# Sheet2.net
KiCad netlist of a schematic drawn in Altium Designer
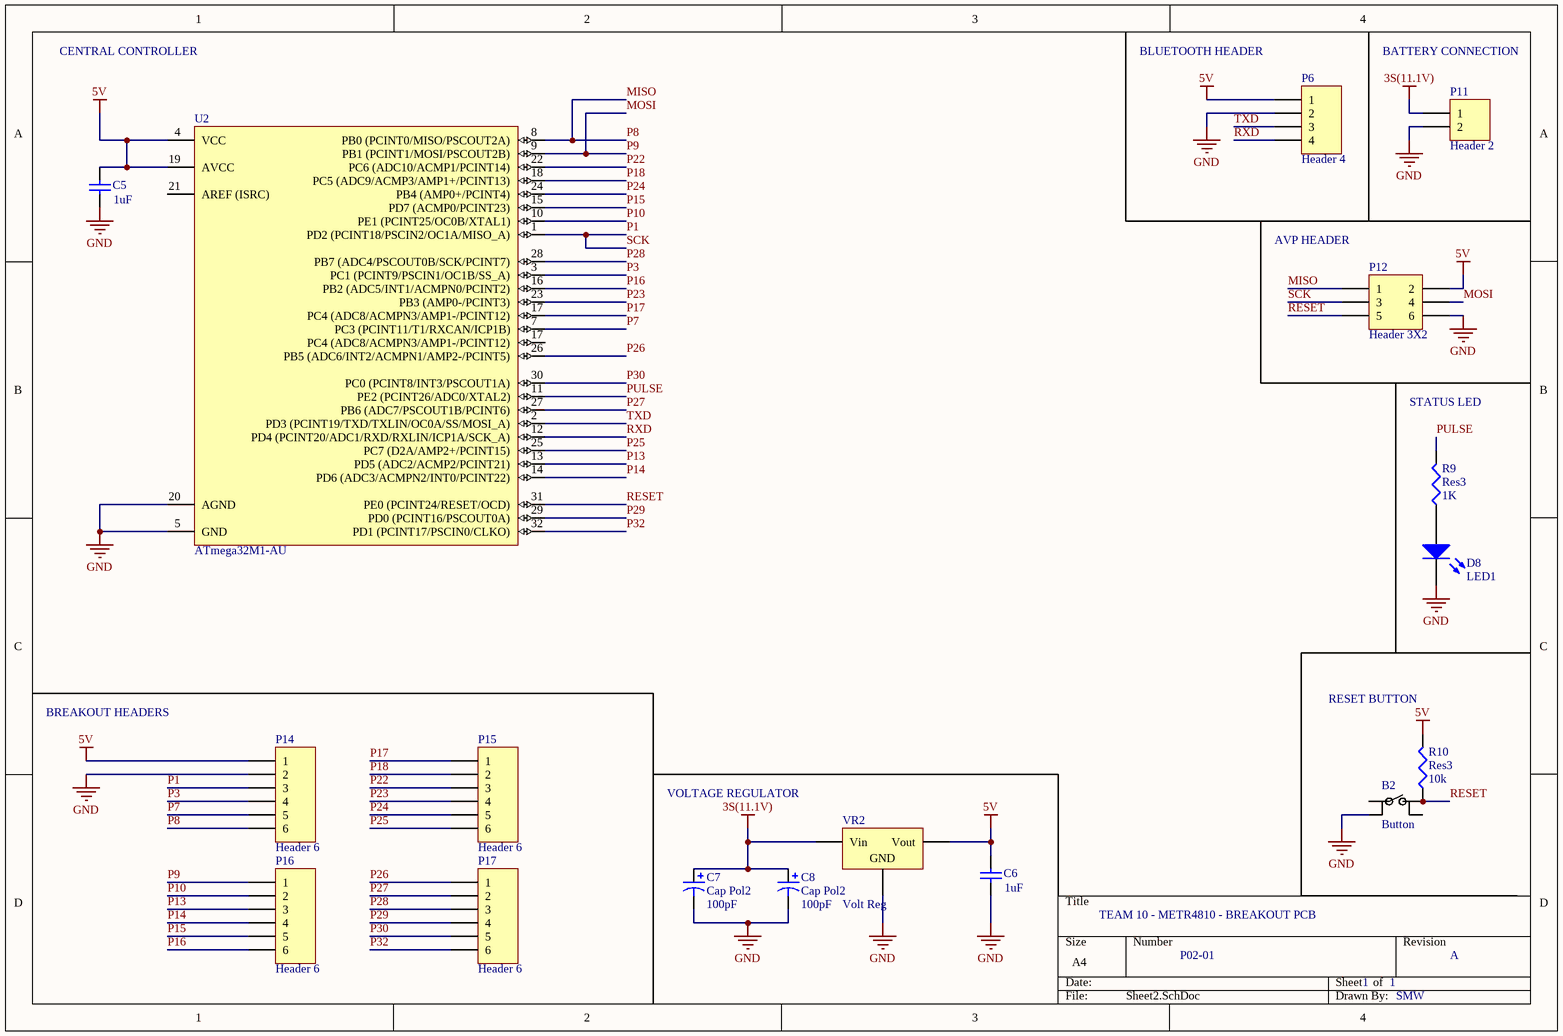
[diagram p0: Sheet2.SchDoc]

(export (version "E")
  (design (tool "Eeschema 10.0.6"))
  (components
    (comp (ref "B2")
      (value "Button")
      (footprint "SMT Tactile Button")
      (libsource (lib "WillsSchematicLibrary") (part "Switch"))
    )
    (comp (ref "C5")
      (value "1uF")
      (footprint "1608[0603]")
      (description "Capacitor")
      (fields (field (name "Comment") "Cap") (field (name "PUBLISHER") "Altium Limited"))
      (libsource (lib "Miscellaneous Devices") (part "Cap"))
    )
    (comp (ref "C6")
      (value "1uF")
      (footprint "1608[0603]")
      (description "Capacitor")
      (fields (field (name "Comment") "Cap") (field (name "PUBLISHER") "Altium Limited"))
      (libsource (lib "Miscellaneous Devices") (part "Cap"))
    )
    (comp (ref "C7")
      (value "Cap Pol2")
      (footprint "CAPAE9983X105M")
      (description "Polarized Capacitor (Axial)")
      (fields (field (name "ALTIUM_VALUE") "100pF") (field (name "PUBLISHER") "Altium Limited"))
      (libsource (lib "Miscellaneous Devices") (part "Cap Pol2"))
    )
    (comp (ref "C8")
      (value "Cap Pol2")
      (footprint "CAPAE9983X105M")
      (description "Polarized Capacitor (Axial)")
      (fields (field (name "ALTIUM_VALUE") "100pF") (field (name "PUBLISHER") "Altium Limited"))
      (libsource (lib "Miscellaneous Devices") (part "Cap Pol2"))
    )
    (comp (ref "D8")
      (value "LED1")
      (footprint "L0603")
      (description "Typical RED GaAs LED")
      (fields (field (name "PUBLISHER") "Altium Limited"))
      (libsource (lib "Miscellaneous Devices") (part "LED1"))
    )
    (comp (ref "P6")
      (value "Header 4")
      (footprint "HDR1X4")
      (description "Header, 4-Pin")
      (fields (field (name "PUBLISHER") "Altium Limited"))
      (libsource (lib "Miscellaneous Connectors") (part "Header 4"))
    )
    (comp (ref "P11")
      (value "Header 2")
      (footprint "HDR1X2")
      (description "Header, 2-Pin")
      (fields (field (name "PUBLISHER") "Altium Limited"))
      (libsource (lib "Miscellaneous Connectors") (part "Header 2"))
    )
    (comp (ref "P12")
      (value "Header 3X2")
      (footprint "HDR2X3")
      (description "Header, 3-Pin, Dual row")
      (fields (field (name "PUBLISHER") "Altium Limited"))
      (libsource (lib "Miscellaneous Connectors") (part "Header 3X2"))
    )
    (comp (ref "P14")
      (value "Header 6")
      (footprint "HDR1X6")
      (description "Header, 6-Pin")
      (fields (field (name "PUBLISHER") "Altium Limited"))
      (libsource (lib "Miscellaneous Connectors") (part "Header 6"))
    )
    (comp (ref "P15")
      (value "Header 6")
      (footprint "HDR1X6")
      (description "Header, 6-Pin")
      (fields (field (name "PUBLISHER") "Altium Limited"))
      (libsource (lib "Miscellaneous Connectors") (part "Header 6"))
    )
    (comp (ref "P16")
      (value "Header 6")
      (footprint "HDR1X6")
      (description "Header, 6-Pin")
      (fields (field (name "PUBLISHER") "Altium Limited"))
      (libsource (lib "Miscellaneous Connectors") (part "Header 6"))
    )
    (comp (ref "P17")
      (value "Header 6")
      (footprint "HDR1X6")
      (description "Header, 6-Pin")
      (fields (field (name "PUBLISHER") "Altium Limited"))
      (libsource (lib "Miscellaneous Connectors") (part "Header 6"))
    )
    (comp (ref "R9")
      (value "Res3")
      (footprint "J1-0603")
      (description "Resistor")
      (fields (field (name "ALTIUM_VALUE") "1K") (field (name "PUBLISHER") "Altium Limited"))
      (libsource (lib "Miscellaneous Devices") (part "Res3"))
    )
    (comp (ref "R10")
      (value "Res3")
      (footprint "J1-0603")
      (description "Resistor")
      (fields (field (name "ALTIUM_VALUE") "10k") (field (name "PUBLISHER") "Altium Limited"))
      (libsource (lib "Miscellaneous Devices") (part "Res3"))
    )
    (comp (ref "U2")
      (value "ATmega32M1-AU")
      (footprint "32A_L")
      (libsource (lib "Atmel Microcontroller AVR Automotive") (part "ATmega32M1-AU"))
    )
    (comp (ref "VR2")
      (value "Volt Reg")
      (footprint "D2PAK_N")
      (description "Voltage Regulator")
      (fields (field (name "PUBLISHER") "Altium Limited"))
      (libsource (lib "Miscellaneous Devices") (part "Volt Reg"))
    )
  )
  (nets
    (net (code "1") (name "/MISO") (class "Default")
      (node (ref "P12") (pin "1") (pinfunction "1_1") (pintype "passive"))
      (node (ref "P14") (pin "6") (pinfunction "6_6") (pintype "passive"))
      (node (ref "U2") (pin "8") (pinfunction "PB0_(PCINT0/MISO/PSCOUT2A)_8") (pintype "bidirectional"))
    )
    (net (code "2") (name "/MOSI") (class "Default")
      (node (ref "P12") (pin "4") (pinfunction "4_4") (pintype "passive"))
      (node (ref "P16") (pin "1") (pinfunction "1_1") (pintype "passive"))
      (node (ref "U2") (pin "9") (pinfunction "PB1_(PCINT1/MOSI/PSCOUT2B)_9") (pintype "bidirectional"))
    )
    (net (code "3") (name "/P1") (class "Default")
      (node (ref "P12") (pin "3") (pinfunction "3_3") (pintype "passive"))
      (node (ref "P14") (pin "3") (pinfunction "3_3") (pintype "passive"))
      (node (ref "U2") (pin "1") (pinfunction "PD2_(PCINT18/PSCIN2/OC1A/MISO_A)_1") (pintype "bidirectional"))
    )
    (net (code "4") (name "/P3") (class "Default")
      (node (ref "P14") (pin "4") (pinfunction "4_4") (pintype "passive"))
      (node (ref "U2") (pin "3") (pinfunction "PC1_(PCINT9/PSCIN1/OC1B/SS_A)_3") (pintype "bidirectional"))
    )
    (net (code "5") (name "/P7") (class "Default")
      (node (ref "P14") (pin "5") (pinfunction "5_5") (pintype "passive"))
      (node (ref "U2") (pin "7") (pinfunction "PC3_(PCINT11/T1/RXCAN/ICP1B)_7") (pintype "bidirectional"))
    )
    (net (code "6") (name "/P10") (class "Default")
      (node (ref "P16") (pin "2") (pinfunction "2_2") (pintype "passive"))
      (node (ref "U2") (pin "10") (pinfunction "PE1_(PCINT25/OC0B/XTAL1)_10") (pintype "bidirectional"))
    )
    (net (code "7") (name "/P13") (class "Default")
      (node (ref "P16") (pin "3") (pinfunction "3_3") (pintype "passive"))
      (node (ref "U2") (pin "13") (pinfunction "PD5_(ADC2/ACMP2/PCINT21)_13") (pintype "bidirectional"))
    )
    (net (code "8") (name "/P14") (class "Default")
      (node (ref "P16") (pin "4") (pinfunction "4_4") (pintype "passive"))
      (node (ref "U2") (pin "14") (pinfunction "PD6_(ADC3/ACMPN2/INT0/PCINT22)_14") (pintype "bidirectional"))
    )
    (net (code "9") (name "/P15") (class "Default")
      (node (ref "P16") (pin "5") (pinfunction "5_5") (pintype "passive"))
      (node (ref "U2") (pin "15") (pinfunction "PD7_(ACMP0/PCINT23)_15") (pintype "bidirectional"))
    )
    (net (code "10") (name "/P16") (class "Default")
      (node (ref "P16") (pin "6") (pinfunction "6_6") (pintype "passive"))
      (node (ref "U2") (pin "16") (pinfunction "PB2_(ADC5/INT1/ACMPN0/PCINT2)_16") (pintype "bidirectional"))
    )
    (net (code "11") (name "/P17") (class "Default")
      (node (ref "P15") (pin "1") (pinfunction "1_1") (pintype "passive"))
      (node (ref "U2") (pin "17") (pinfunction "PC4_(ADC8/ACMPN3/AMP1-/PCINT12)_17") (pintype "bidirectional"))
    )
    (net (code "12") (name "/P18") (class "Default")
      (node (ref "P15") (pin "2") (pinfunction "2_2") (pintype "passive"))
      (node (ref "U2") (pin "18") (pinfunction "PC5_(ADC9/ACMP3/AMP1+/PCINT13)_18") (pintype "bidirectional"))
    )
    (net (code "13") (name "/P22") (class "Default")
      (node (ref "P15") (pin "3") (pinfunction "3_3") (pintype "passive"))
      (node (ref "U2") (pin "22") (pinfunction "PC6_(ADC10/ACMP1/PCINT14)_22") (pintype "bidirectional"))
    )
    (net (code "14") (name "/P23") (class "Default")
      (node (ref "P15") (pin "4") (pinfunction "4_4") (pintype "passive"))
      (node (ref "U2") (pin "23") (pinfunction "PB3_(AMP0-/PCINT3)_23") (pintype "bidirectional"))
    )
    (net (code "15") (name "/P24") (class "Default")
      (node (ref "P15") (pin "5") (pinfunction "5_5") (pintype "passive"))
      (node (ref "U2") (pin "24") (pinfunction "PB4_(AMP0+/PCINT4)_24") (pintype "bidirectional"))
    )
    (net (code "16") (name "/P25") (class "Default")
      (node (ref "P15") (pin "6") (pinfunction "6_6") (pintype "passive"))
      (node (ref "U2") (pin "25") (pinfunction "PC7_(D2A/AMP2+/PCINT15)_25") (pintype "bidirectional"))
    )
    (net (code "17") (name "/P26") (class "Default")
      (node (ref "P17") (pin "1") (pinfunction "1_1") (pintype "passive"))
      (node (ref "U2") (pin "26") (pinfunction "PB5_(ADC6/INT2/ACMPN1/AMP2-/PCINT5)_26") (pintype "bidirectional"))
    )
    (net (code "18") (name "/P27") (class "Default")
      (node (ref "P17") (pin "2") (pinfunction "2_2") (pintype "passive"))
      (node (ref "U2") (pin "27") (pinfunction "PB6_(ADC7/PSCOUT1B/PCINT6)_27") (pintype "bidirectional"))
    )
    (net (code "19") (name "/P28") (class "Default")
      (node (ref "P17") (pin "3") (pinfunction "3_3") (pintype "passive"))
      (node (ref "U2") (pin "28") (pinfunction "PB7_(ADC4/PSCOUT0B/SCK/PCINT7)_28") (pintype "bidirectional"))
    )
    (net (code "20") (name "/P29") (class "Default")
      (node (ref "P17") (pin "4") (pinfunction "4_4") (pintype "passive"))
      (node (ref "U2") (pin "29") (pinfunction "PD0_(PCINT16/PSCOUT0A)_29") (pintype "bidirectional"))
    )
    (net (code "21") (name "/P30") (class "Default")
      (node (ref "P17") (pin "5") (pinfunction "5_5") (pintype "passive"))
      (node (ref "U2") (pin "30") (pinfunction "PC0_(PCINT8/INT3/PSCOUT1A)_30") (pintype "bidirectional"))
    )
    (net (code "22") (name "/P32") (class "Default")
      (node (ref "P17") (pin "6") (pinfunction "6_6") (pintype "passive"))
      (node (ref "U2") (pin "32") (pinfunction "PD1_(PCINT17/PSCIN0/CLKO)_32") (pintype "bidirectional"))
    )
    (net (code "23") (name "/PULSE") (class "Default")
      (node (ref "R9") (pin "2") (pinfunction "2_2") (pintype "passive"))
      (node (ref "U2") (pin "11") (pinfunction "PE2_(PCINT26/ADC0/XTAL2)_11") (pintype "bidirectional"))
    )
    (net (code "24") (name "/RESET") (class "Default")
      (node (ref "B2") (pin "4") (pinfunction "4_4") (pintype "passive"))
      (node (ref "P12") (pin "5") (pinfunction "5_5") (pintype "passive"))
      (node (ref "R10") (pin "1") (pinfunction "1_1") (pintype "passive"))
      (node (ref "U2") (pin "31") (pinfunction "PE0_(PCINT24/RESET/OCD)_31") (pintype "bidirectional"))
    )
    (net (code "25") (name "/RXD") (class "Default")
      (node (ref "P6") (pin "4") (pinfunction "4_4") (pintype "passive"))
      (node (ref "U2") (pin "12") (pinfunction "PD4_(PCINT20/ADC1/RXD/RXLIN/ICP1A/SCK_A)_12") (pintype "bidirectional"))
    )
    (net (code "26") (name "/TXD") (class "Default")
      (node (ref "P6") (pin "3") (pinfunction "3_3") (pintype "passive"))
      (node (ref "U2") (pin "2") (pinfunction "PD3_(PCINT19/TXD/TXLIN/OC0A/SS/MOSI_A)_2") (pintype "bidirectional"))
    )
    (net (code "27") (name "3S(11.1V)") (class "Default")
      (node (ref "C7") (pin "1") (pinfunction "1_1") (pintype "passive"))
      (node (ref "C8") (pin "1") (pinfunction "1_1") (pintype "passive"))
      (node (ref "P11") (pin "1") (pinfunction "1_1") (pintype "passive"))
      (node (ref "VR2") (pin "1") (pinfunction "Vin_1") (pintype "passive"))
    )
    (net (code "28") (name "5V") (class "Default")
      (node (ref "C5") (pin "2") (pinfunction "2_2") (pintype "passive"))
      (node (ref "C6") (pin "2") (pinfunction "2_2") (pintype "passive"))
      (node (ref "P12") (pin "2") (pinfunction "2_2") (pintype "passive"))
      (node (ref "P14") (pin "1") (pinfunction "1_1") (pintype "passive"))
      (node (ref "P6") (pin "1") (pinfunction "1_1") (pintype "passive"))
      (node (ref "R10") (pin "2") (pinfunction "2_2") (pintype "passive"))
      (node (ref "U2") (pin "19") (pinfunction "AVCC_19") (pintype "power_in"))
      (node (ref "U2") (pin "4") (pinfunction "VCC_4") (pintype "power_in"))
      (node (ref "VR2") (pin "3") (pinfunction "Vout_3") (pintype "passive"))
    )
    (net (code "29") (name "GND") (class "Default")
      (node (ref "B2") (pin "2") (pinfunction "2_2") (pintype "passive"))
      (node (ref "C5") (pin "1") (pinfunction "1_1") (pintype "passive"))
      (node (ref "C6") (pin "1") (pinfunction "1_1") (pintype "passive"))
      (node (ref "C7") (pin "2") (pinfunction "2_2") (pintype "passive"))
      (node (ref "C8") (pin "2") (pinfunction "2_2") (pintype "passive"))
      (node (ref "D8") (pin "2") (pinfunction "K_2") (pintype "passive"))
      (node (ref "P11") (pin "2") (pinfunction "2_2") (pintype "passive"))
      (node (ref "P12") (pin "6") (pinfunction "6_6") (pintype "passive"))
      (node (ref "P14") (pin "2") (pinfunction "2_2") (pintype "passive"))
      (node (ref "P6") (pin "2") (pinfunction "2_2") (pintype "passive"))
      (node (ref "U2") (pin "20") (pinfunction "AGND_20") (pintype "power_in"))
      (node (ref "U2") (pin "5") (pinfunction "GND_5") (pintype "power_in"))
      (node (ref "VR2") (pin "2") (pinfunction "GND_2") (pintype "passive"))
    )
    (net (code "30") (name "Net-(D8-A)") (class "Default")
      (node (ref "D8") (pin "1") (pinfunction "A_1") (pintype "passive"))
      (node (ref "R9") (pin "1") (pinfunction "1_1") (pintype "passive"))
    )
    (net (code "31") (name "unconnected-(B2-Pad1)") (class "Default")
      (node (ref "B2") (pin "1") (pinfunction "1_1") (pintype "passive"))
    )
    (net (code "32") (name "unconnected-(B2-Pad3)") (class "Default")
      (node (ref "B2") (pin "3") (pinfunction "3_3") (pintype "passive"))
    )
    (net (code "33") (name "unconnected-(U2-AREF_(ISRC)-Pad21)") (class "Default")
      (node (ref "U2") (pin "21") (pinfunction "AREF_(ISRC)_21") (pintype "power_in"))
    )
    (net (code "34") (name "unconnected-(U2-PC4_(ADC8{slash}ACMPN3{slash}AMP1-{slash}PCINT12)-Pad17)") (class "Default")
      (node (ref "U2") (pin "17") (pinfunction "PC4_(ADC8/ACMPN3/AMP1-/PCINT12)_17") (pintype "bidirectional"))
    )
  )
)
